# Gadgeteer_Sponsor_Board.net
KiCad netlist of a schematic drawn in EAGLE
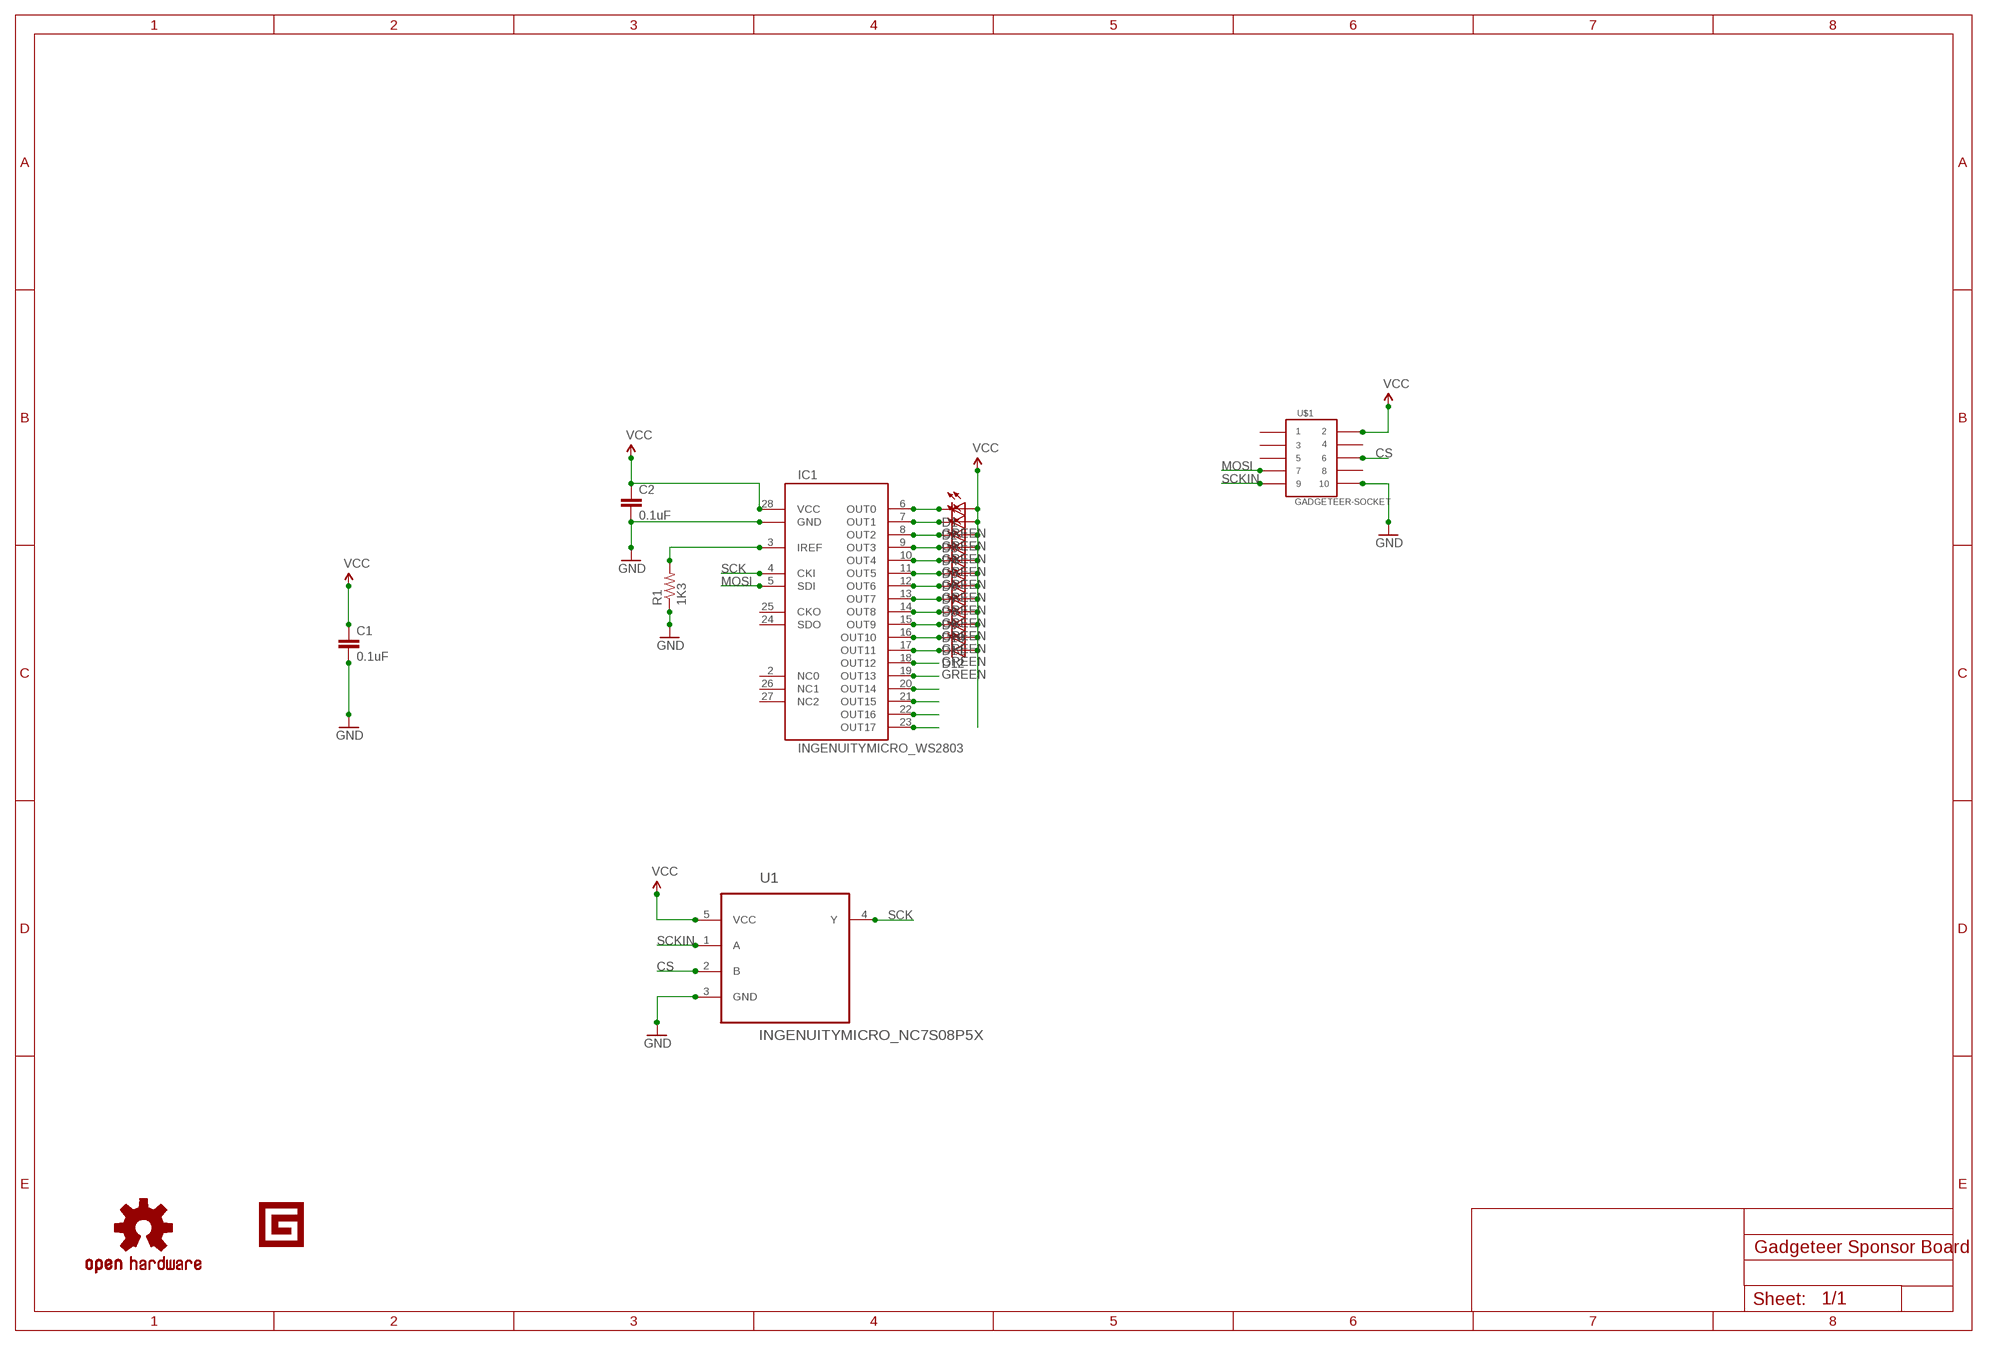
[diagram p0: schematic, sheet 1]

(export (version "E")
  (design (tool "Eeschema 10.0.6"))
  (components
    (comp (ref "C1")
      (value "0.1uF")
      (footprint "eagle-import:SPARKFUN_0603-CAP")
      (libsource (lib "eagle-import") (part "SPARKFUN_CAP0603-CAP"))
    )
    (comp (ref "C2")
      (value "0.1uF")
      (footprint "eagle-import:SPARKFUN_0603-CAP")
      (libsource (lib "eagle-import") (part "SPARKFUN_CAP0603-CAP"))
    )
    (comp (ref "D1")
      (value "GREEN")
      (footprint "eagle-import:LED-0603")
      (libsource (lib "eagle-import") (part "LED-GREEN0603"))
    )
    (comp (ref "D2")
      (value "GREEN")
      (footprint "eagle-import:LED-0603")
      (fields (field (name "PROD_ID") "DIO-00821"))
      (libsource (lib "eagle-import") (part "LED-GREEN0603"))
    )
    (comp (ref "D3")
      (value "GREEN")
      (footprint "eagle-import:LED-0603")
      (libsource (lib "eagle-import") (part "LED-GREEN0603"))
    )
    (comp (ref "D4")
      (value "GREEN")
      (footprint "eagle-import:LED-0603")
      (libsource (lib "eagle-import") (part "LED-GREEN0603"))
    )
    (comp (ref "D5")
      (value "GREEN")
      (footprint "eagle-import:LED-0603")
      (libsource (lib "eagle-import") (part "LED-GREEN0603"))
    )
    (comp (ref "D6")
      (value "GREEN")
      (footprint "eagle-import:LED-0603")
      (libsource (lib "eagle-import") (part "LED-GREEN0603"))
    )
    (comp (ref "D7")
      (value "GREEN")
      (footprint "eagle-import:LED-0603")
      (libsource (lib "eagle-import") (part "LED-GREEN0603"))
    )
    (comp (ref "D8")
      (value "GREEN")
      (footprint "eagle-import:LED-0603")
      (libsource (lib "eagle-import") (part "LED-GREEN0603"))
    )
    (comp (ref "D9")
      (value "GREEN")
      (footprint "eagle-import:LED-0603")
      (libsource (lib "eagle-import") (part "LED-GREEN0603"))
    )
    (comp (ref "D10")
      (value "GREEN")
      (footprint "eagle-import:LED-0603")
      (libsource (lib "eagle-import") (part "LED-GREEN0603"))
    )
    (comp (ref "D11")
      (value "GREEN")
      (footprint "eagle-import:LED-0603")
      (libsource (lib "eagle-import") (part "LED-GREEN0603"))
    )
    (comp (ref "D12")
      (value "GREEN")
      (footprint "eagle-import:LED-0603")
      (libsource (lib "eagle-import") (part "LED-GREEN0603"))
    )
    (comp (ref "IC1")
      (value "INGENUITYMICRO_WS2803")
      (footprint "eagle-import:INGENUITYMICRO_SO28W")
      (libsource (lib "eagle-import") (part "INGENUITYMICRO_WS2803"))
    )
    (comp (ref "LOGO1")
      (value "OSHW-LOGOL")
      (footprint "eagle-import:OSHW-LOGO-L")
      (libsource (lib "eagle-import") (part "OSHW-LOGOL"))
    )
    (comp (ref "R1")
      (value "1K3")
      (footprint "eagle-import:RESISTOR_R0603")
      (libsource (lib "eagle-import") (part "RESISTOR_R-US_R0603"))
    )
    (comp (ref "U$1")
      (value "GADGETEER-SOCKET")
      (footprint "eagle-import:2X5_1.27MM")
      (libsource (lib "eagle-import") (part "GADGETEER-SOCKET"))
    )
    (comp (ref "U$2")
      (value "INGENUITYMICRO_LOGO_LOGO-GADGETEER-NORMAL")
      (footprint "eagle-import:INGENUITYMICRO_LOGO_GADGETEER-SILK")
      (libsource (lib "eagle-import") (part "INGENUITYMICRO_LOGO_LOGO-GADGETEER-NORMAL"))
    )
    (comp (ref "U1")
      (value "INGENUITYMICRO_NC7S08P5X")
      (footprint "eagle-import:INGENUITYMICRO_SOT65P210X110-5N")
      (fields (field (name "MPN") "NC7S08P5X"))
      (libsource (lib "eagle-import") (part "INGENUITYMICRO_NC7S08P5X"))
    )
  )
  (nets
    (net (code "1") (name "/CS") (class "Default")
      (node (ref "U$1") (pin "6") (pinfunction "P$6_6") (pintype "bidirectional"))
      (node (ref "U1") (pin "2") (pinfunction "B_2") (pintype "input"))
    )
    (net (code "2") (name "/MOSI") (class "Default")
      (node (ref "IC1") (pin "5") (pinfunction "SDI_5") (pintype "input"))
      (node (ref "U$1") (pin "7") (pinfunction "P$7_7") (pintype "bidirectional"))
    )
    (net (code "3") (name "/SCK") (class "Default")
      (node (ref "IC1") (pin "4") (pinfunction "CKI_4") (pintype "input"))
      (node (ref "U1") (pin "4") (pinfunction "Y_4") (pintype "output"))
    )
    (net (code "4") (name "/SCKIN") (class "Default")
      (node (ref "U$1") (pin "9") (pinfunction "P$9_9") (pintype "bidirectional"))
      (node (ref "U1") (pin "1") (pinfunction "A_1") (pintype "input"))
    )
    (net (code "5") (name "GND") (class "Default")
      (node (ref "C1") (pin "2") (pinfunction "2_2") (pintype "passive"))
      (node (ref "C2") (pin "2") (pinfunction "2_2") (pintype "passive"))
      (node (ref "IC1") (pin "1") (pinfunction "GND_1") (pintype "power_in"))
      (node (ref "R1") (pin "1") (pinfunction "1_1") (pintype "passive"))
      (node (ref "U$1") (pin "10") (pinfunction "P$10_10") (pintype "bidirectional"))
      (node (ref "U1") (pin "3") (pinfunction "GND_3") (pintype "passive"))
    )
    (net (code "6") (name "Net-(IC1-IREF)") (class "Default")
      (node (ref "IC1") (pin "3") (pinfunction "IREF_3") (pintype "input"))
      (node (ref "R1") (pin "2") (pinfunction "2_2") (pintype "passive"))
    )
    (net (code "7") (name "Net-(IC1-OUT0)") (class "Default")
      (node (ref "D1") (pin "C") (pinfunction "C_C") (pintype "passive"))
      (node (ref "IC1") (pin "6") (pinfunction "OUT0_6") (pintype "output"))
    )
    (net (code "8") (name "Net-(IC1-OUT1)") (class "Default")
      (node (ref "D2") (pin "C") (pinfunction "C_C") (pintype "passive"))
      (node (ref "IC1") (pin "7") (pinfunction "OUT1_7") (pintype "output"))
    )
    (net (code "9") (name "Net-(IC1-OUT2)") (class "Default")
      (node (ref "D3") (pin "C") (pinfunction "C_C") (pintype "passive"))
      (node (ref "IC1") (pin "8") (pinfunction "OUT2_8") (pintype "output"))
    )
    (net (code "10") (name "Net-(IC1-OUT3)") (class "Default")
      (node (ref "D4") (pin "C") (pinfunction "C_C") (pintype "passive"))
      (node (ref "IC1") (pin "9") (pinfunction "OUT3_9") (pintype "output"))
    )
    (net (code "11") (name "Net-(IC1-OUT4)") (class "Default")
      (node (ref "D5") (pin "C") (pinfunction "C_C") (pintype "passive"))
      (node (ref "IC1") (pin "10") (pinfunction "OUT4_10") (pintype "output"))
    )
    (net (code "12") (name "Net-(IC1-OUT5)") (class "Default")
      (node (ref "D6") (pin "C") (pinfunction "C_C") (pintype "passive"))
      (node (ref "IC1") (pin "11") (pinfunction "OUT5_11") (pintype "output"))
    )
    (net (code "13") (name "Net-(IC1-OUT6)") (class "Default")
      (node (ref "D7") (pin "C") (pinfunction "C_C") (pintype "passive"))
      (node (ref "IC1") (pin "12") (pinfunction "OUT6_12") (pintype "output"))
    )
    (net (code "14") (name "Net-(IC1-OUT7)") (class "Default")
      (node (ref "D8") (pin "C") (pinfunction "C_C") (pintype "passive"))
      (node (ref "IC1") (pin "13") (pinfunction "OUT7_13") (pintype "output"))
    )
    (net (code "15") (name "Net-(IC1-OUT8)") (class "Default")
      (node (ref "D9") (pin "C") (pinfunction "C_C") (pintype "passive"))
      (node (ref "IC1") (pin "14") (pinfunction "OUT8_14") (pintype "output"))
    )
    (net (code "16") (name "Net-(IC1-OUT9)") (class "Default")
      (node (ref "D10") (pin "C") (pinfunction "C_C") (pintype "passive"))
      (node (ref "IC1") (pin "15") (pinfunction "OUT9_15") (pintype "output"))
    )
    (net (code "17") (name "Net-(IC1-OUT10)") (class "Default")
      (node (ref "D11") (pin "C") (pinfunction "C_C") (pintype "passive"))
      (node (ref "IC1") (pin "16") (pinfunction "OUT10_16") (pintype "output"))
    )
    (net (code "18") (name "Net-(IC1-OUT11)") (class "Default")
      (node (ref "D12") (pin "C") (pinfunction "C_C") (pintype "passive"))
      (node (ref "IC1") (pin "17") (pinfunction "OUT11_17") (pintype "output"))
    )
    (net (code "19") (name "VCC") (class "Default")
      (node (ref "C1") (pin "1") (pinfunction "1_1") (pintype "passive"))
      (node (ref "C2") (pin "1") (pinfunction "1_1") (pintype "passive"))
      (node (ref "D1") (pin "A") (pinfunction "A_A") (pintype "passive"))
      (node (ref "D10") (pin "A") (pinfunction "A_A") (pintype "passive"))
      (node (ref "D11") (pin "A") (pinfunction "A_A") (pintype "passive"))
      (node (ref "D12") (pin "A") (pinfunction "A_A") (pintype "passive"))
      (node (ref "D2") (pin "A") (pinfunction "A_A") (pintype "passive"))
      (node (ref "D3") (pin "A") (pinfunction "A_A") (pintype "passive"))
      (node (ref "D4") (pin "A") (pinfunction "A_A") (pintype "passive"))
      (node (ref "D5") (pin "A") (pinfunction "A_A") (pintype "passive"))
      (node (ref "D6") (pin "A") (pinfunction "A_A") (pintype "passive"))
      (node (ref "D7") (pin "A") (pinfunction "A_A") (pintype "passive"))
      (node (ref "D8") (pin "A") (pinfunction "A_A") (pintype "passive"))
      (node (ref "D9") (pin "A") (pinfunction "A_A") (pintype "passive"))
      (node (ref "IC1") (pin "28") (pinfunction "VCC_28") (pintype "power_in"))
      (node (ref "U$1") (pin "2") (pinfunction "P$2_2") (pintype "bidirectional"))
      (node (ref "U1") (pin "5") (pinfunction "VCC_5") (pintype "power_in"))
    )
    (net (code "20") (name "unconnected-(IC1-CKO-Pad25)") (class "Default")
      (node (ref "IC1") (pin "25") (pinfunction "CKO_25") (pintype "output"))
    )
    (net (code "21") (name "unconnected-(IC1-NC0-Pad2)") (class "Default")
      (node (ref "IC1") (pin "2") (pinfunction "NC0_2") (pintype "no_connect"))
    )
    (net (code "22") (name "unconnected-(IC1-NC1-Pad26)") (class "Default")
      (node (ref "IC1") (pin "26") (pinfunction "NC1_26") (pintype "no_connect"))
    )
    (net (code "23") (name "unconnected-(IC1-NC2-Pad27)") (class "Default")
      (node (ref "IC1") (pin "27") (pinfunction "NC2_27") (pintype "no_connect"))
    )
    (net (code "24") (name "unconnected-(IC1-OUT12-Pad18)") (class "Default")
      (node (ref "IC1") (pin "18") (pinfunction "OUT12_18") (pintype "output"))
    )
    (net (code "25") (name "unconnected-(IC1-OUT13-Pad19)") (class "Default")
      (node (ref "IC1") (pin "19") (pinfunction "OUT13_19") (pintype "output"))
    )
    (net (code "26") (name "unconnected-(IC1-OUT14-Pad20)") (class "Default")
      (node (ref "IC1") (pin "20") (pinfunction "OUT14_20") (pintype "output"))
    )
    (net (code "27") (name "unconnected-(IC1-OUT15-Pad21)") (class "Default")
      (node (ref "IC1") (pin "21") (pinfunction "OUT15_21") (pintype "output"))
    )
    (net (code "28") (name "unconnected-(IC1-OUT16-Pad22)") (class "Default")
      (node (ref "IC1") (pin "22") (pinfunction "OUT16_22") (pintype "output"))
    )
    (net (code "29") (name "unconnected-(IC1-OUT17-Pad23)") (class "Default")
      (node (ref "IC1") (pin "23") (pinfunction "OUT17_23") (pintype "output"))
    )
    (net (code "30") (name "unconnected-(IC1-SDO-Pad24)") (class "Default")
      (node (ref "IC1") (pin "24") (pinfunction "SDO_24") (pintype "output"))
    )
    (net (code "31") (name "unconnected-(U$1-P$1-Pad1)") (class "Default")
      (node (ref "U$1") (pin "1") (pinfunction "P$1_1") (pintype "bidirectional"))
    )
    (net (code "32") (name "unconnected-(U$1-P$3-Pad3)") (class "Default")
      (node (ref "U$1") (pin "3") (pinfunction "P$3_3") (pintype "bidirectional"))
    )
    (net (code "33") (name "unconnected-(U$1-P$4-Pad4)") (class "Default")
      (node (ref "U$1") (pin "4") (pinfunction "P$4_4") (pintype "bidirectional"))
    )
    (net (code "34") (name "unconnected-(U$1-P$5-Pad5)") (class "Default")
      (node (ref "U$1") (pin "5") (pinfunction "P$5_5") (pintype "bidirectional"))
    )
    (net (code "35") (name "unconnected-(U$1-P$8-Pad8)") (class "Default")
      (node (ref "U$1") (pin "8") (pinfunction "P$8_8") (pintype "bidirectional"))
    )
  )
)
